# ProPrj__STM32_PCB_2025-02-11.net
KiCad netlist of a schematic drawn in EasyEDA Pro
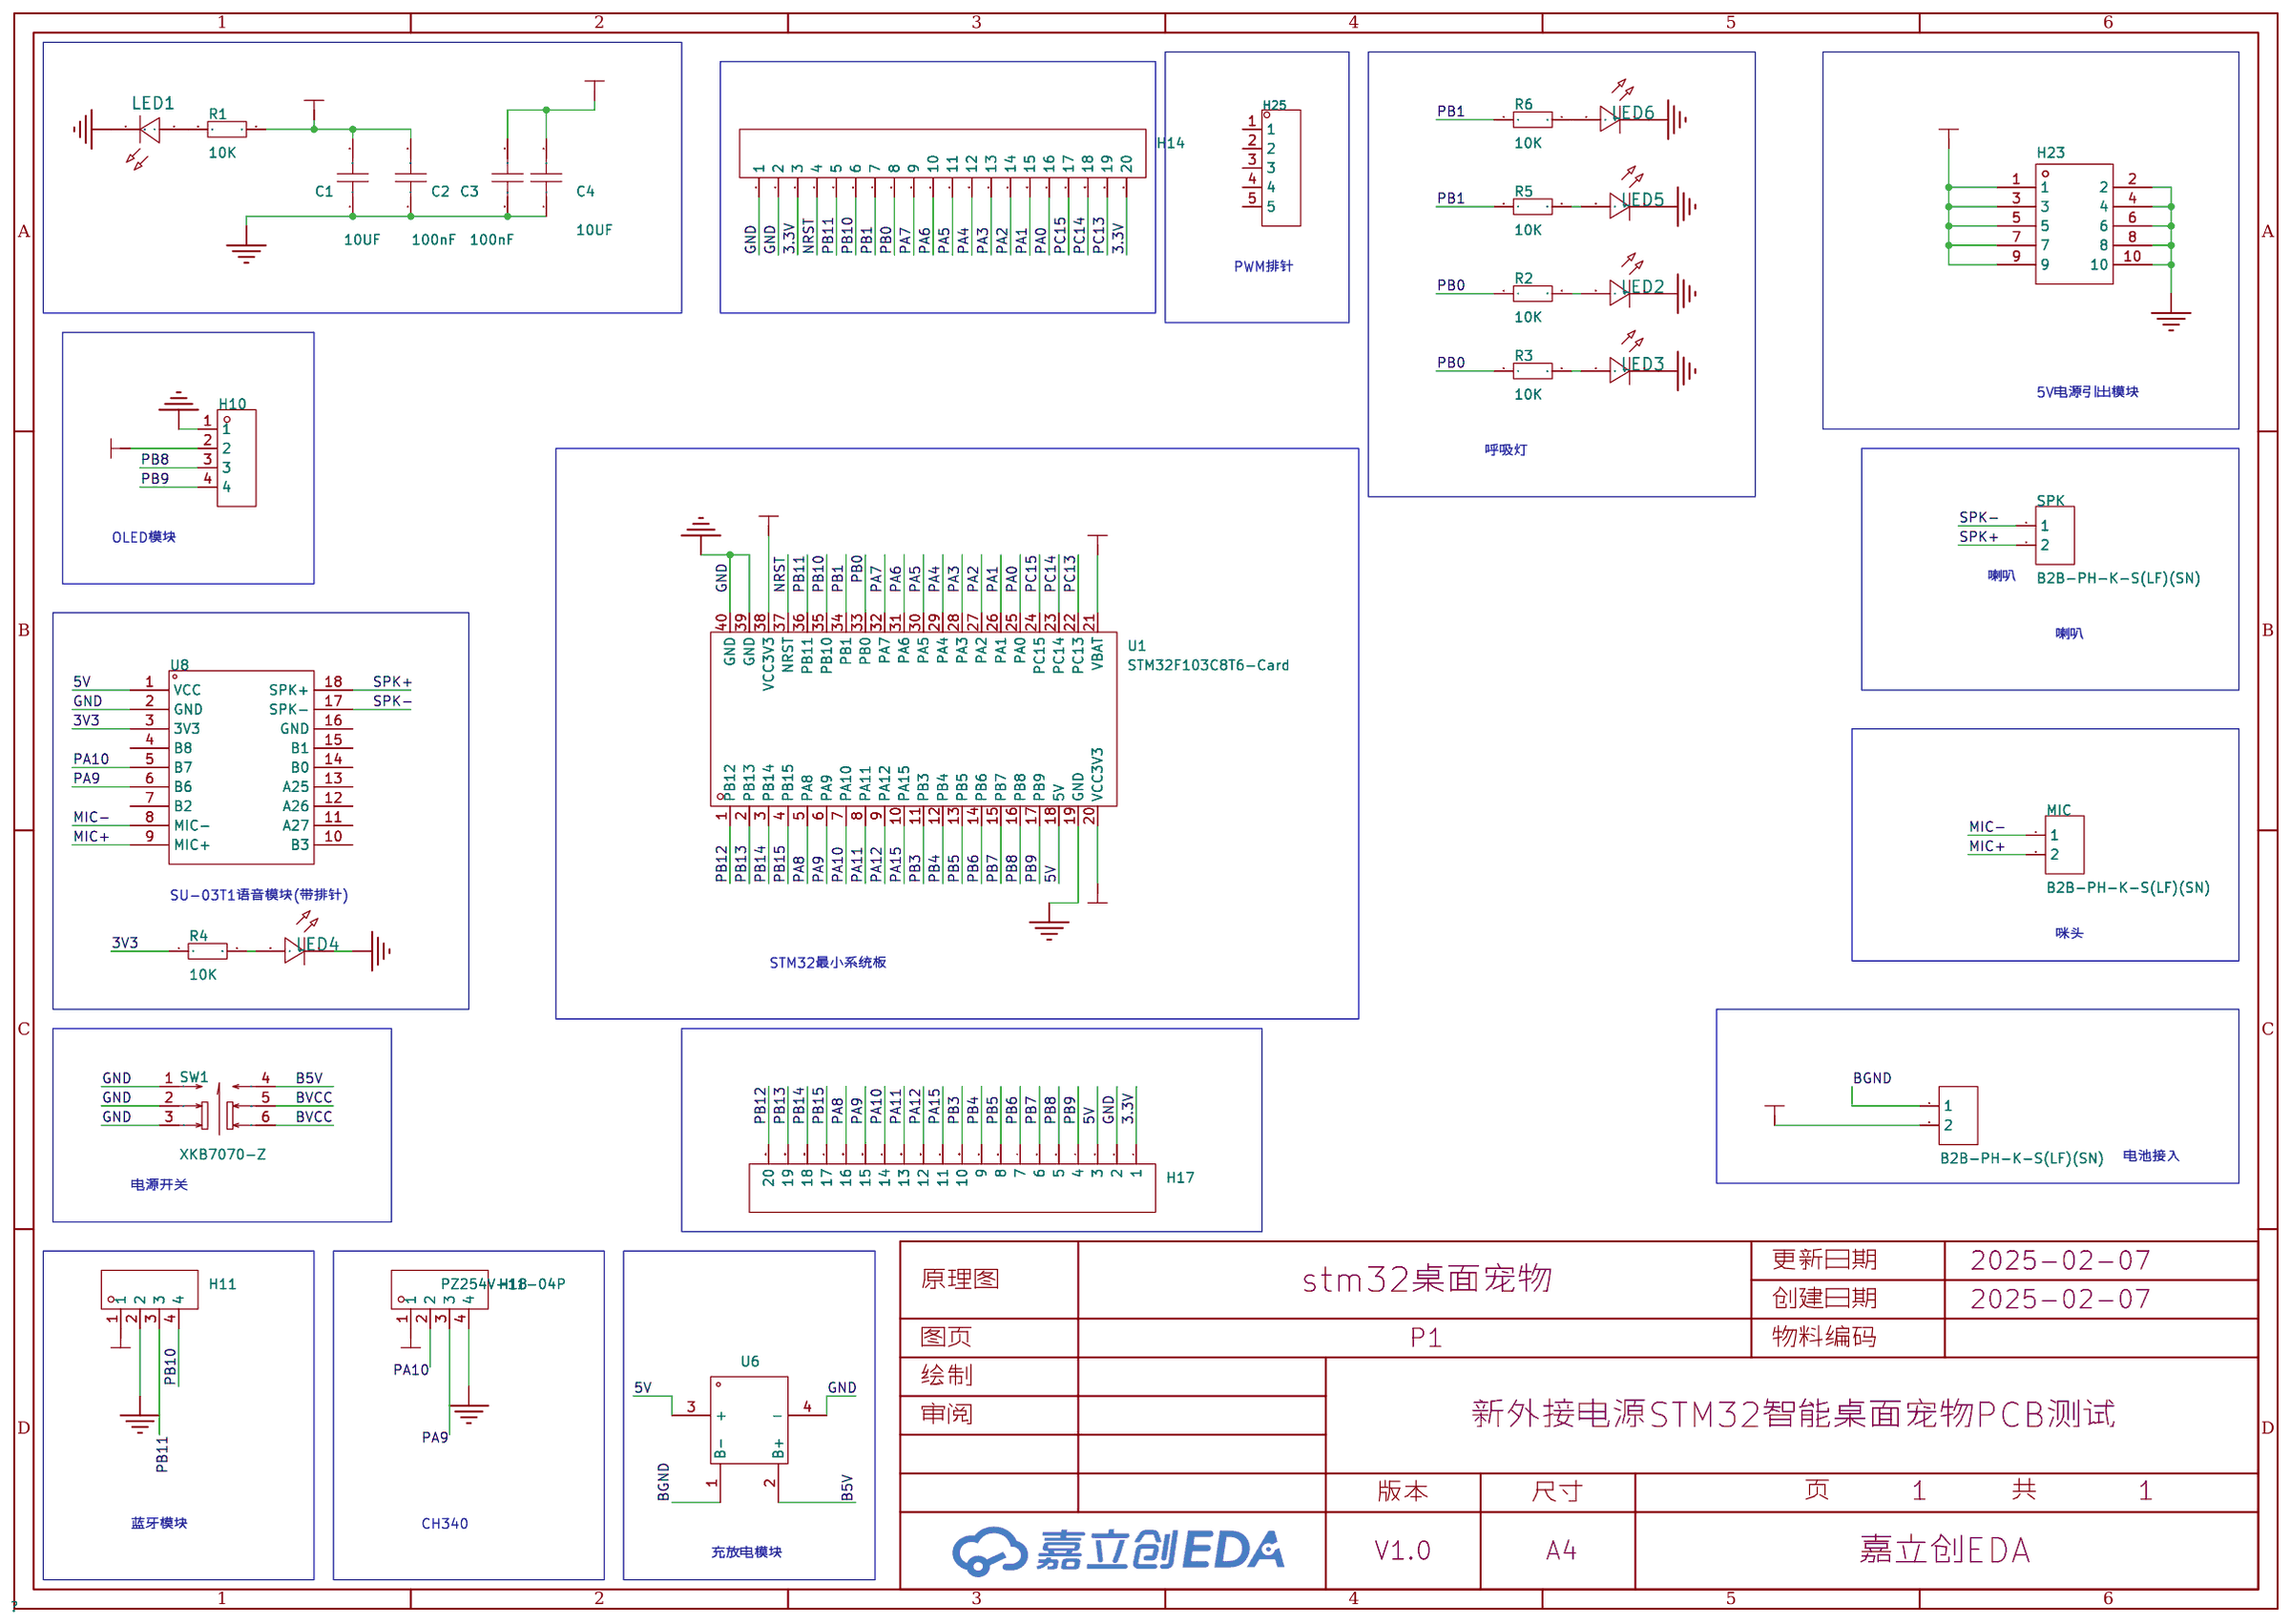
[diagram p0: schematic sheet]

(export (version "E")
  (design (tool "Eeschema 10.0.6"))
  (components
    (comp (ref "Battery")
      (value "B2B-PH-K-S(LF)(SN)")
      (footprint "easyedapro:HDR-TH_2P-P2.54-V-F")
      (fields (field (name "Manufacturer") "JST"))
      (libsource (lib "easyedapro") (part "Header-Female-2.54_1x2"))
    )
    (comp (ref "C1")
      (value "10UF")
      (footprint "easyedapro:C0603")
      (libsource (lib "easyedapro") (part "CapAcitance"))
    )
    (comp (ref "C2")
      (value "100nF")
      (footprint "easyedapro:C0603")
      (libsource (lib "easyedapro") (part "CapAcitance"))
    )
    (comp (ref "C3")
      (value "100nF")
      (footprint "easyedapro:C0603")
      (libsource (lib "easyedapro") (part "CapAcitance"))
    )
    (comp (ref "C4")
      (value "10UF")
      (footprint "easyedapro:C0603")
      (libsource (lib "easyedapro") (part "CapAcitance"))
    )
    (comp (ref "H10")
      (value "~")
      (footprint "easyedapro:HDR-TH_4P-P2.54-V-F")
      (libsource (lib "easyedapro") (part "2.54-1*4P母"))
    )
    (comp (ref "H11")
      (value "~")
      (footprint "easyedapro:HDR-TH_4P-P2.54-V-F")
      (libsource (lib "easyedapro") (part "2.54-1*4P母"))
    )
    (comp (ref "H14")
      (value "~")
      (footprint "easyedapro:HDR-TH_20P-P2.54-V-F")
      (libsource (lib "easyedapro") (part "HDR-F_2.54_1x20P"))
    )
    (comp (ref "H17")
      (value "~")
      (footprint "easyedapro:HDR-TH_20P-P2.54-V-F")
      (libsource (lib "easyedapro") (part "HDR-F_2.54_1x20P"))
    )
    (comp (ref "H18")
      (value "PZ254V-11-04P")
      (footprint "easyedapro:HDR-TH_4P-P2.54-V-F")
      (fields (field (name "Manufacturer") "XFCN(兴飞)"))
      (libsource (lib "easyedapro") (part "2.54-1*4P母"))
    )
    (comp (ref "H23")
      (value "~")
      (footprint "easyedapro:HDR-TH_10P-P2.54-V-M-R2-C5-S2.54")
      (libsource (lib "easyedapro") (part "HDR-M-2.54_2x5"))
    )
    (comp (ref "H25")
      (value "~")
      (footprint "easyedapro:HDR-TH_5P-P2.54-V-M")
      (libsource (lib "easyedapro") (part "MTP125-1105S1"))
    )
    (comp (ref "LED1")
      (value "~")
      (footprint "easyedapro:LED_0805")
      (libsource (lib "easyedapro") (part "LED_R"))
    )
    (comp (ref "LED2")
      (value "~")
      (footprint "easyedapro:LED_0805")
      (libsource (lib "easyedapro") (part "LED_R"))
    )
    (comp (ref "LED3")
      (value "~")
      (footprint "easyedapro:LED_0805")
      (libsource (lib "easyedapro") (part "LED_R"))
    )
    (comp (ref "LED4")
      (value "~")
      (footprint "easyedapro:LED_0805")
      (libsource (lib "easyedapro") (part "LED_R"))
    )
    (comp (ref "LED5")
      (value "~")
      (footprint "easyedapro:LED_0805")
      (libsource (lib "easyedapro") (part "LED_R"))
    )
    (comp (ref "LED6")
      (value "~")
      (footprint "easyedapro:LED_0805")
      (libsource (lib "easyedapro") (part "LED_R"))
    )
    (comp (ref "MIC")
      (value "B2B-PH-K-S(LF)(SN)")
      (footprint "easyedapro:HDR-TH_2P-P2.54-V-F")
      (fields (field (name "Manufacturer") "JST"))
      (libsource (lib "easyedapro") (part "Header-Female-2.54_1x2"))
    )
    (comp (ref "R1") (value "10K") (footprint "easyedapro:R0603") (libsource (lib "easyedapro") (part "电阻")))
    (comp (ref "R2") (value "10K") (footprint "easyedapro:R0603") (libsource (lib "easyedapro") (part "电阻")))
    (comp (ref "R3") (value "10K") (footprint "easyedapro:R0603") (libsource (lib "easyedapro") (part "电阻")))
    (comp (ref "R4") (value "10K") (footprint "easyedapro:R0603") (libsource (lib "easyedapro") (part "电阻")))
    (comp (ref "R5") (value "10K") (footprint "easyedapro:R0603") (libsource (lib "easyedapro") (part "电阻")))
    (comp (ref "R6") (value "10K") (footprint "easyedapro:R0603") (libsource (lib "easyedapro") (part "电阻")))
    (comp (ref "SPK")
      (value "B2B-PH-K-S(LF)(SN)")
      (footprint "easyedapro:HDR-TH_2P-P2.54-V-F")
      (fields (field (name "Manufacturer") "JST"))
      (libsource (lib "easyedapro") (part "Header-Female-2.54_1x2"))
    )
    (comp (ref "SW1")
      (value "XKB7070-Z")
      (footprint "easyedapro:SW-TH_6P-L7.0-W7.0-P2.00")
      (description "自锁/无锁:自锁;安装方式:直插;触点电流:100mA;额定电压 (AC):250V;额定电压 (DC):30V;带灯:不带;作用力:160gf;机械寿命:10万次;")
      (fields (field (name "Manufacturer") "XKB Connectivity(中国星坤)"))
      (libsource (lib "easyedapro") (part "XKB7070-Z"))
    )
    (comp (ref "U1")
      (value "STM32F103C8T6-Card")
      (footprint "easyedapro:CONN-TH_L53.3-W22.9_STM32F103C8T6-CARD")
      (libsource (lib "easyedapro") (part "STM32F103C8T6-CARD"))
    )
    (comp (ref "U6") (value "~") (libsource (lib "easyedapro") (part "5V充放电模块")))
    (comp (ref "U8")
      (value "~")
      (footprint "easyedapro:SU-03T带排针")
      (libsource (lib "easyedapro") (part "SU-03T带排针"))
    )
  )
  (nets
    (net (code "1") (name "/3V3") (class "Default")
      (node (ref "R4") (pin "1") (pinfunction "1_1") (pintype "input"))
      (node (ref "U8") (pin "3") (pinfunction "3V3_3") (pintype "input"))
    )
    (net (code "2") (name "/B5V") (class "Default")
      (node (ref "SW1") (pin "4") (pinfunction "4_4") (pintype "unspecified"))
      (node (ref "U6") (pin "2") (pinfunction "B+_2") (pintype "input"))
    )
    (net (code "3") (name "/BGND") (class "Default")
      (node (ref "Battery") (pin "1") (pinfunction "1_1") (pintype "input"))
      (node (ref "U6") (pin "1") (pinfunction "B-_1") (pintype "input"))
    )
    (net (code "4") (name "/MIC+") (class "Default")
      (node (ref "MIC") (pin "2") (pinfunction "2_2") (pintype "input"))
      (node (ref "U8") (pin "9") (pinfunction "MIC+_9") (pintype "input"))
    )
    (net (code "5") (name "/MIC-") (class "Default")
      (node (ref "MIC") (pin "1") (pinfunction "1_1") (pintype "input"))
      (node (ref "U8") (pin "8") (pinfunction "MIC-_8") (pintype "input"))
    )
    (net (code "6") (name "/NRST") (class "Default")
      (node (ref "H14") (pin "4") (pinfunction "4_4") (pintype "input"))
      (node (ref "U1") (pin "37") (pinfunction "NRST_37") (pintype "unspecified"))
    )
    (net (code "7") (name "/PA0") (class "Default")
      (node (ref "H14") (pin "16") (pinfunction "16_16") (pintype "input"))
      (node (ref "U1") (pin "25") (pinfunction "PA0_25") (pintype "unspecified"))
    )
    (net (code "8") (name "/PA1") (class "Default")
      (node (ref "H14") (pin "15") (pinfunction "15_15") (pintype "input"))
      (node (ref "U1") (pin "26") (pinfunction "PA1_26") (pintype "unspecified"))
    )
    (net (code "9") (name "/PA2") (class "Default")
      (node (ref "H14") (pin "14") (pinfunction "14_14") (pintype "input"))
      (node (ref "U1") (pin "27") (pinfunction "PA2_27") (pintype "unspecified"))
    )
    (net (code "10") (name "/PA3") (class "Default")
      (node (ref "H14") (pin "13") (pinfunction "13_13") (pintype "input"))
      (node (ref "U1") (pin "28") (pinfunction "PA3_28") (pintype "unspecified"))
    )
    (net (code "11") (name "/PA4") (class "Default")
      (node (ref "H14") (pin "12") (pinfunction "12_12") (pintype "input"))
      (node (ref "U1") (pin "29") (pinfunction "PA4_29") (pintype "unspecified"))
    )
    (net (code "12") (name "/PA5") (class "Default")
      (node (ref "H14") (pin "11") (pinfunction "11_11") (pintype "input"))
      (node (ref "U1") (pin "30") (pinfunction "PA5_30") (pintype "unspecified"))
    )
    (net (code "13") (name "/PA6") (class "Default")
      (node (ref "H14") (pin "10") (pinfunction "10_10") (pintype "input"))
      (node (ref "U1") (pin "31") (pinfunction "PA6_31") (pintype "unspecified"))
    )
    (net (code "14") (name "/PA7") (class "Default")
      (node (ref "H14") (pin "9") (pinfunction "9_9") (pintype "input"))
      (node (ref "U1") (pin "32") (pinfunction "PA7_32") (pintype "unspecified"))
    )
    (net (code "15") (name "/PA8") (class "Default")
      (node (ref "H17") (pin "16") (pinfunction "16_16") (pintype "input"))
      (node (ref "U1") (pin "5") (pinfunction "PA8_5") (pintype "unspecified"))
    )
    (net (code "16") (name "/PA9") (class "Default")
      (node (ref "H17") (pin "15") (pinfunction "15_15") (pintype "input"))
      (node (ref "H18") (pin "3") (pinfunction "3_3") (pintype "unspecified"))
      (node (ref "U1") (pin "6") (pinfunction "PA9_6") (pintype "unspecified"))
      (node (ref "U8") (pin "6") (pinfunction "B6_6") (pintype "input"))
    )
    (net (code "17") (name "/PA10") (class "Default")
      (node (ref "H17") (pin "14") (pinfunction "14_14") (pintype "input"))
      (node (ref "H18") (pin "2") (pinfunction "2_2") (pintype "unspecified"))
      (node (ref "U1") (pin "7") (pinfunction "PA10_7") (pintype "unspecified"))
      (node (ref "U8") (pin "5") (pinfunction "B7_5") (pintype "input"))
    )
    (net (code "18") (name "/PA11") (class "Default")
      (node (ref "H17") (pin "13") (pinfunction "13_13") (pintype "input"))
      (node (ref "U1") (pin "8") (pinfunction "PA11_8") (pintype "unspecified"))
    )
    (net (code "19") (name "/PA12") (class "Default")
      (node (ref "H17") (pin "12") (pinfunction "12_12") (pintype "input"))
      (node (ref "U1") (pin "9") (pinfunction "PA12_9") (pintype "unspecified"))
    )
    (net (code "20") (name "/PA15") (class "Default")
      (node (ref "H17") (pin "11") (pinfunction "11_11") (pintype "input"))
      (node (ref "U1") (pin "10") (pinfunction "PA15_10") (pintype "unspecified"))
    )
    (net (code "21") (name "/PB0") (class "Default")
      (node (ref "H14") (pin "8") (pinfunction "8_8") (pintype "input"))
      (node (ref "R2") (pin "1") (pinfunction "1_1") (pintype "input"))
      (node (ref "R3") (pin "1") (pinfunction "1_1") (pintype "input"))
      (node (ref "U1") (pin "33") (pinfunction "PB0_33") (pintype "unspecified"))
    )
    (net (code "22") (name "/PB1") (class "Default")
      (node (ref "H14") (pin "7") (pinfunction "7_7") (pintype "input"))
      (node (ref "R5") (pin "1") (pinfunction "1_1") (pintype "input"))
      (node (ref "R6") (pin "1") (pinfunction "1_1") (pintype "input"))
      (node (ref "U1") (pin "34") (pinfunction "PB1_34") (pintype "unspecified"))
    )
    (net (code "23") (name "/PB3") (class "Default")
      (node (ref "H17") (pin "10") (pinfunction "10_10") (pintype "input"))
      (node (ref "U1") (pin "11") (pinfunction "PB3_11") (pintype "unspecified"))
    )
    (net (code "24") (name "/PB4") (class "Default")
      (node (ref "H17") (pin "9") (pinfunction "9_9") (pintype "input"))
      (node (ref "U1") (pin "12") (pinfunction "PB4_12") (pintype "unspecified"))
    )
    (net (code "25") (name "/PB5") (class "Default")
      (node (ref "H17") (pin "8") (pinfunction "8_8") (pintype "input"))
      (node (ref "U1") (pin "13") (pinfunction "PB5_13") (pintype "unspecified"))
    )
    (net (code "26") (name "/PB6") (class "Default")
      (node (ref "H17") (pin "7") (pinfunction "7_7") (pintype "input"))
      (node (ref "U1") (pin "14") (pinfunction "PB6_14") (pintype "unspecified"))
    )
    (net (code "27") (name "/PB7") (class "Default")
      (node (ref "H17") (pin "6") (pinfunction "6_6") (pintype "input"))
      (node (ref "U1") (pin "15") (pinfunction "PB7_15") (pintype "unspecified"))
    )
    (net (code "28") (name "/PB8") (class "Default")
      (node (ref "H10") (pin "3") (pinfunction "3_3") (pintype "unspecified"))
      (node (ref "H17") (pin "5") (pinfunction "5_5") (pintype "input"))
      (node (ref "U1") (pin "16") (pinfunction "PB8_16") (pintype "unspecified"))
    )
    (net (code "29") (name "/PB9") (class "Default")
      (node (ref "H10") (pin "4") (pinfunction "4_4") (pintype "unspecified"))
      (node (ref "H17") (pin "4") (pinfunction "4_4") (pintype "input"))
      (node (ref "U1") (pin "17") (pinfunction "PB9_17") (pintype "unspecified"))
    )
    (net (code "30") (name "/PB10") (class "Default")
      (node (ref "H11") (pin "4") (pinfunction "4_4") (pintype "unspecified"))
      (node (ref "H14") (pin "6") (pinfunction "6_6") (pintype "input"))
      (node (ref "U1") (pin "35") (pinfunction "PB10_35") (pintype "unspecified"))
    )
    (net (code "31") (name "/PB11") (class "Default")
      (node (ref "H11") (pin "3") (pinfunction "3_3") (pintype "unspecified"))
      (node (ref "H14") (pin "5") (pinfunction "5_5") (pintype "input"))
      (node (ref "U1") (pin "36") (pinfunction "PB11_36") (pintype "unspecified"))
    )
    (net (code "32") (name "/PB12") (class "Default")
      (node (ref "H17") (pin "20") (pinfunction "20_20") (pintype "input"))
      (node (ref "U1") (pin "1") (pinfunction "PB12_1") (pintype "unspecified"))
    )
    (net (code "33") (name "/PB13") (class "Default")
      (node (ref "H17") (pin "19") (pinfunction "19_19") (pintype "input"))
      (node (ref "U1") (pin "2") (pinfunction "PB13_2") (pintype "unspecified"))
    )
    (net (code "34") (name "/PB14") (class "Default")
      (node (ref "H17") (pin "18") (pinfunction "18_18") (pintype "input"))
      (node (ref "U1") (pin "3") (pinfunction "PB14_3") (pintype "unspecified"))
    )
    (net (code "35") (name "/PB15") (class "Default")
      (node (ref "H17") (pin "17") (pinfunction "17_17") (pintype "input"))
      (node (ref "U1") (pin "4") (pinfunction "PB15_4") (pintype "unspecified"))
    )
    (net (code "36") (name "/PC13") (class "Default")
      (node (ref "H14") (pin "19") (pinfunction "19_19") (pintype "input"))
      (node (ref "U1") (pin "22") (pinfunction "PC13_22") (pintype "unspecified"))
    )
    (net (code "37") (name "/PC14") (class "Default")
      (node (ref "H14") (pin "18") (pinfunction "18_18") (pintype "input"))
      (node (ref "U1") (pin "23") (pinfunction "PC14_23") (pintype "unspecified"))
    )
    (net (code "38") (name "/PC15") (class "Default")
      (node (ref "H14") (pin "17") (pinfunction "17_17") (pintype "input"))
      (node (ref "U1") (pin "24") (pinfunction "PC15_24") (pintype "unspecified"))
    )
    (net (code "39") (name "/SPK+") (class "Default")
      (node (ref "SPK") (pin "2") (pinfunction "2_2") (pintype "input"))
      (node (ref "U8") (pin "18") (pinfunction "SPK+_18") (pintype "input"))
    )
    (net (code "40") (name "/SPK-") (class "Default")
      (node (ref "SPK") (pin "1") (pinfunction "1_1") (pintype "input"))
      (node (ref "U8") (pin "17") (pinfunction "SPK-_17") (pintype "input"))
    )
    (net (code "41") (name "3.3V") (class "Default")
      (node (ref "C3") (pin "2") (pinfunction "2_2") (pintype "input"))
      (node (ref "C4") (pin "2") (pinfunction "2_2") (pintype "input"))
      (node (ref "H10") (pin "2") (pinfunction "2_2") (pintype "unspecified"))
      (node (ref "H11") (pin "1") (pinfunction "1_1") (pintype "unspecified"))
      (node (ref "H14") (pin "20") (pinfunction "20_20") (pintype "input"))
      (node (ref "H14") (pin "3") (pinfunction "3_3") (pintype "input"))
      (node (ref "H17") (pin "1") (pinfunction "1_1") (pintype "input"))
      (node (ref "U1") (pin "20") (pinfunction "VCC3V3_20") (pintype "unspecified"))
      (node (ref "U1") (pin "21") (pinfunction "VBAT_21") (pintype "unspecified"))
      (node (ref "U1") (pin "38") (pinfunction "VCC3V3_38") (pintype "unspecified"))
    )
    (net (code "42") (name "5V") (class "Default")
      (node (ref "C1") (pin "2") (pinfunction "2_2") (pintype "input"))
      (node (ref "C2") (pin "2") (pinfunction "2_2") (pintype "input"))
      (node (ref "H17") (pin "3") (pinfunction "3_3") (pintype "input"))
      (node (ref "H18") (pin "1") (pinfunction "1_1") (pintype "unspecified"))
      (node (ref "H23") (pin "1") (pinfunction "1_1") (pintype "input"))
      (node (ref "H23") (pin "3") (pinfunction "3_3") (pintype "input"))
      (node (ref "H23") (pin "5") (pinfunction "5_5") (pintype "input"))
      (node (ref "H23") (pin "7") (pinfunction "7_7") (pintype "input"))
      (node (ref "H23") (pin "9") (pinfunction "9_9") (pintype "input"))
      (node (ref "R1") (pin "1") (pinfunction "1_1") (pintype "input"))
      (node (ref "U1") (pin "18") (pinfunction "5V_18") (pintype "unspecified"))
      (node (ref "U6") (pin "3") (pinfunction "+_3") (pintype "input"))
      (node (ref "U8") (pin "1") (pinfunction "VCC_1") (pintype "input"))
    )
    (net (code "43") (name "BVCC") (class "Default")
      (node (ref "Battery") (pin "2") (pinfunction "2_2") (pintype "input"))
      (node (ref "SW1") (pin "5") (pinfunction "5_5") (pintype "unspecified"))
      (node (ref "SW1") (pin "6") (pinfunction "6_6") (pintype "unspecified"))
    )
    (net (code "44") (name "GND") (class "Default")
      (node (ref "C1") (pin "1") (pinfunction "1_1") (pintype "input"))
      (node (ref "C2") (pin "1") (pinfunction "1_1") (pintype "input"))
      (node (ref "C3") (pin "1") (pinfunction "1_1") (pintype "input"))
      (node (ref "C4") (pin "1") (pinfunction "1_1") (pintype "input"))
      (node (ref "H10") (pin "1") (pinfunction "1_1") (pintype "unspecified"))
      (node (ref "H11") (pin "2") (pinfunction "2_2") (pintype "unspecified"))
      (node (ref "H14") (pin "1") (pinfunction "1_1") (pintype "input"))
      (node (ref "H14") (pin "2") (pinfunction "2_2") (pintype "input"))
      (node (ref "H17") (pin "2") (pinfunction "2_2") (pintype "input"))
      (node (ref "H18") (pin "4") (pinfunction "4_4") (pintype "unspecified"))
      (node (ref "H23") (pin "10") (pinfunction "10_10") (pintype "input"))
      (node (ref "H23") (pin "2") (pinfunction "2_2") (pintype "input"))
      (node (ref "H23") (pin "4") (pinfunction "4_4") (pintype "input"))
      (node (ref "H23") (pin "6") (pinfunction "6_6") (pintype "input"))
      (node (ref "H23") (pin "8") (pinfunction "8_8") (pintype "input"))
      (node (ref "LED1") (pin "1") (pinfunction "C_1") (pintype "input"))
      (node (ref "LED2") (pin "1") (pinfunction "C_1") (pintype "input"))
      (node (ref "LED3") (pin "1") (pinfunction "C_1") (pintype "input"))
      (node (ref "LED4") (pin "1") (pinfunction "C_1") (pintype "input"))
      (node (ref "LED5") (pin "1") (pinfunction "C_1") (pintype "input"))
      (node (ref "LED6") (pin "1") (pinfunction "C_1") (pintype "input"))
      (node (ref "SW1") (pin "1") (pinfunction "1_1") (pintype "unspecified"))
      (node (ref "SW1") (pin "2") (pinfunction "2_2") (pintype "unspecified"))
      (node (ref "SW1") (pin "3") (pinfunction "3_3") (pintype "unspecified"))
      (node (ref "U1") (pin "19") (pinfunction "GND_19") (pintype "unspecified"))
      (node (ref "U1") (pin "39") (pinfunction "GND_39") (pintype "unspecified"))
      (node (ref "U1") (pin "40") (pinfunction "GND_40") (pintype "unspecified"))
      (node (ref "U6") (pin "4") (pinfunction "-_4") (pintype "input"))
      (node (ref "U8") (pin "2") (pinfunction "GND_2") (pintype "input"))
    )
    (net (code "45") (name "Net-(LED1-A)") (class "Default")
      (node (ref "LED1") (pin "2") (pinfunction "A_2") (pintype "input"))
      (node (ref "R1") (pin "2") (pinfunction "2_2") (pintype "input"))
    )
    (net (code "46") (name "Net-(LED2-A)") (class "Default")
      (node (ref "LED2") (pin "2") (pinfunction "A_2") (pintype "input"))
      (node (ref "R2") (pin "2") (pinfunction "2_2") (pintype "input"))
    )
    (net (code "47") (name "Net-(LED3-A)") (class "Default")
      (node (ref "LED3") (pin "2") (pinfunction "A_2") (pintype "input"))
      (node (ref "R3") (pin "2") (pinfunction "2_2") (pintype "input"))
    )
    (net (code "48") (name "Net-(LED4-A)") (class "Default")
      (node (ref "LED4") (pin "2") (pinfunction "A_2") (pintype "input"))
      (node (ref "R4") (pin "2") (pinfunction "2_2") (pintype "input"))
    )
    (net (code "49") (name "Net-(LED5-A)") (class "Default")
      (node (ref "LED5") (pin "2") (pinfunction "A_2") (pintype "input"))
      (node (ref "R5") (pin "2") (pinfunction "2_2") (pintype "input"))
    )
    (net (code "50") (name "Net-(LED6-A)") (class "Default")
      (node (ref "LED6") (pin "2") (pinfunction "A_2") (pintype "input"))
      (node (ref "R6") (pin "2") (pinfunction "2_2") (pintype "input"))
    )
    (net (code "51") (name "unconnected-(H25-Pad1)") (class "Default")
      (node (ref "H25") (pin "1") (pinfunction "1_1") (pintype "input"))
    )
    (net (code "52") (name "unconnected-(H25-Pad2)") (class "Default")
      (node (ref "H25") (pin "2") (pinfunction "2_2") (pintype "input"))
    )
    (net (code "53") (name "unconnected-(H25-Pad3)") (class "Default")
      (node (ref "H25") (pin "3") (pinfunction "3_3") (pintype "input"))
    )
    (net (code "54") (name "unconnected-(H25-Pad4)") (class "Default")
      (node (ref "H25") (pin "4") (pinfunction "4_4") (pintype "input"))
    )
    (net (code "55") (name "unconnected-(H25-Pad5)") (class "Default")
      (node (ref "H25") (pin "5") (pinfunction "5_5") (pintype "input"))
    )
    (net (code "56") (name "unconnected-(U8-A25-Pad13)") (class "Default")
      (node (ref "U8") (pin "13") (pinfunction "A25_13") (pintype "input"))
    )
    (net (code "57") (name "unconnected-(U8-A26-Pad12)") (class "Default")
      (node (ref "U8") (pin "12") (pinfunction "A26_12") (pintype "input"))
    )
    (net (code "58") (name "unconnected-(U8-A27-Pad11)") (class "Default")
      (node (ref "U8") (pin "11") (pinfunction "A27_11") (pintype "input"))
    )
    (net (code "59") (name "unconnected-(U8-B0-Pad14)") (class "Default")
      (node (ref "U8") (pin "14") (pinfunction "B0_14") (pintype "input"))
    )
    (net (code "60") (name "unconnected-(U8-B1-Pad15)") (class "Default")
      (node (ref "U8") (pin "15") (pinfunction "B1_15") (pintype "input"))
    )
    (net (code "61") (name "unconnected-(U8-B2-Pad7)") (class "Default")
      (node (ref "U8") (pin "7") (pinfunction "B2_7") (pintype "input"))
    )
    (net (code "62") (name "unconnected-(U8-B3-Pad10)") (class "Default")
      (node (ref "U8") (pin "10") (pinfunction "B3_10") (pintype "input"))
    )
    (net (code "63") (name "unconnected-(U8-B8-Pad4)") (class "Default")
      (node (ref "U8") (pin "4") (pinfunction "B8_4") (pintype "input"))
    )
    (net (code "64") (name "unconnected-(U8-GND-Pad16)") (class "Default")
      (node (ref "U8") (pin "16") (pinfunction "GND_16") (pintype "input"))
    )
  )
)
